# alcohal_sensor_and_send_sms_using_gsm.net
KiCad netlist of a schematic drawn in EAGLE
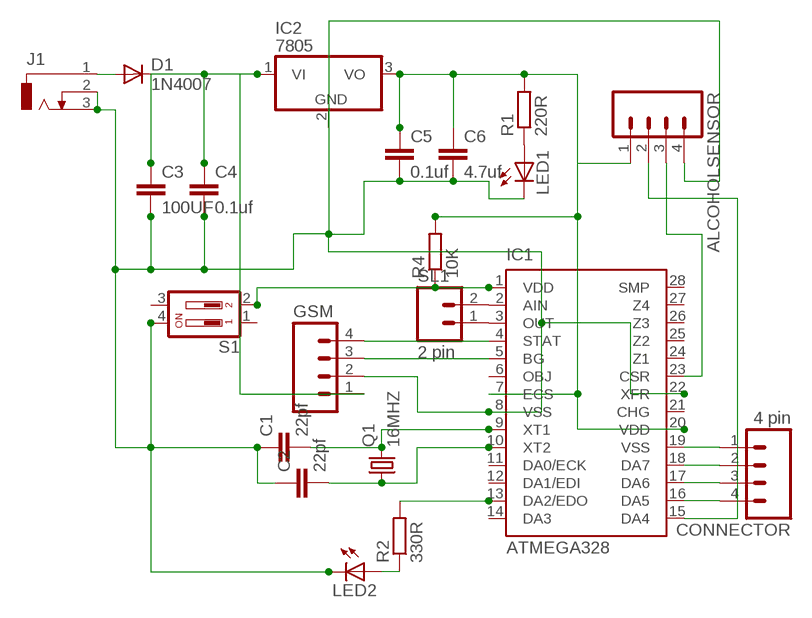
[diagram p0: schematic, sheet 1]

(export (version "E")
  (design (tool "Eeschema 10.0.6"))
  (components
    (comp (ref "ALCOHOLSENSOR")
      (value "M04")
      (footprint "eagle-import:04P")
      (fields (field (name "OC_FARNELL") "unknown") (field (name "OC_NEWARK") "unknown"))
      (libsource (lib "eagle-import") (part "M04"))
    )
    (comp (ref "C1")
      (value "22pf")
      (footprint "eagle-import:C2.5-2")
      (libsource (lib "eagle-import") (part "C2.5/2"))
    )
    (comp (ref "C2")
      (value "22pf")
      (footprint "eagle-import:C2.5-2")
      (libsource (lib "eagle-import") (part "C2.5/2"))
    )
    (comp (ref "C3")
      (value "100UF")
      (footprint "eagle-import:C2.5-2")
      (libsource (lib "eagle-import") (part "C2.5/2"))
    )
    (comp (ref "C4")
      (value "0.1uf")
      (footprint "eagle-import:C2.5-2")
      (libsource (lib "eagle-import") (part "C2.5/2"))
    )
    (comp (ref "C5")
      (value "0.1uf")
      (footprint "eagle-import:C2.5-2")
      (libsource (lib "eagle-import") (part "C2.5/2"))
    )
    (comp (ref "C6")
      (value "4.7uf")
      (footprint "eagle-import:C2.5-2")
      (libsource (lib "eagle-import") (part "C2.5/2"))
    )
    (comp (ref "CONNECTOR")
      (value "4 pin")
      (footprint "eagle-import:04P")
      (fields (field (name "OC_FARNELL") "unknown") (field (name "OC_NEWARK") "unknown"))
      (libsource (lib "eagle-import") (part "M04"))
    )
    (comp (ref "D1")
      (value "1N4007")
      (footprint "eagle-import:DO41-10")
      (libsource (lib "eagle-import") (part "1N4004"))
    )
    (comp (ref "GSM")
      (value "M04")
      (footprint "eagle-import:04P")
      (libsource (lib "eagle-import") (part "M04"))
    )
    (comp (ref "IC1")
      (value "ATMEGA328")
      (footprint "eagle-import:DIL28-3")
      (libsource (lib "eagle-import") (part "QT9701BD"))
    )
    (comp (ref "IC2")
      (value "7805")
      (footprint "eagle-import:TO220V")
      (libsource (lib "eagle-import") (part "78TV6"))
    )
    (comp (ref "J1")
      (value "DCJ0303")
      (footprint "eagle-import:DCJ0303")
      (libsource (lib "eagle-import") (part "DCJ0303"))
    )
    (comp (ref "LED1")
      (value "LED3MM")
      (footprint "eagle-import:LED3MM")
      (libsource (lib "eagle-import") (part "LED3MM"))
    )
    (comp (ref "LED2")
      (value "LED3MM")
      (footprint "eagle-import:LED3MM")
      (libsource (lib "eagle-import") (part "LED3MM"))
    )
    (comp (ref "Q1")
      (value "16MHZ")
      (footprint "eagle-import:HC49_S")
      (libsource (lib "eagle-import") (part "CRYSTALHC49S"))
    )
    (comp (ref "R1")
      (value "220R")
      (footprint "eagle-import:0207_10")
      (libsource (lib "eagle-import") (part "R-EU_0207/10"))
    )
    (comp (ref "R2")
      (value "330R")
      (footprint "eagle-import:0207_10")
      (libsource (lib "eagle-import") (part "R-EU_0207/10"))
    )
    (comp (ref "R4")
      (value "10K")
      (footprint "eagle-import:0207_10")
      (libsource (lib "eagle-import") (part "R-EU_0207/10"))
    )
    (comp (ref "S1")
      (value "DP02")
      (footprint "eagle-import:DP-02")
      (fields (field (name "MPN") "MCDP02"))
      (libsource (lib "eagle-import") (part "DP02"))
    )
    (comp (ref "SL1")
      (value "2 pin")
      (footprint "eagle-import:02P")
      (libsource (lib "eagle-import") (part "M02"))
    )
  )
  (nets
    (net (code "1") (name "Net-(CONNECTOR-Pad1)") (class "Default")
      (node (ref "CONNECTOR") (pin "1") (pinfunction "1_1") (pintype "passive"))
      (node (ref "IC1") (pin "19") (pinfunction "VSS_19") (pintype "input"))
    )
    (net (code "2") (name "Net-(D1-PadA)") (class "Default")
      (node (ref "D1") (pin "A") (pinfunction "A_A") (pintype "passive"))
      (node (ref "J1") (pin "1") (pinfunction "1_1") (pintype "passive"))
    )
    (net (code "3") (name "Net-(IC1-AIN)") (class "Default")
      (node (ref "IC1") (pin "2") (pinfunction "AIN_2") (pintype "input"))
      (node (ref "SL1") (pin "2") (pinfunction "2_2") (pintype "passive"))
    )
    (net (code "4") (name "Net-(IC1-BG)") (class "Default")
      (node (ref "GSM") (pin "3") (pinfunction "3_3") (pintype "passive"))
      (node (ref "IC1") (pin "5") (pinfunction "BG_5") (pintype "input"))
    )
    (net (code "5") (name "Net-(IC1-CSR)") (class "Default")
      (node (ref "ALCOHOLSENSOR") (pin "3") (pinfunction "3_3") (pintype "passive"))
      (node (ref "IC1") (pin "23") (pinfunction "CSR_23") (pintype "output"))
    )
    (net (code "6") (name "Net-(IC1-DA2{slash}EDO)") (class "Default")
      (node (ref "IC1") (pin "13") (pinfunction "DA2/EDO_13") (pintype "output"))
      (node (ref "R2") (pin "2") (pinfunction "2_2") (pintype "passive"))
    )
    (net (code "7") (name "Net-(IC1-DA4)") (class "Default")
      (node (ref "ALCOHOLSENSOR") (pin "2") (pinfunction "2_2") (pintype "passive"))
      (node (ref "IC1") (pin "15") (pinfunction "DA4_15") (pintype "output"))
    )
    (net (code "8") (name "Net-(IC1-DA5)") (class "Default")
      (node (ref "CONNECTOR") (pin "4") (pinfunction "4_4") (pintype "passive"))
      (node (ref "IC1") (pin "16") (pinfunction "DA5_16") (pintype "output"))
    )
    (net (code "9") (name "Net-(IC1-DA6)") (class "Default")
      (node (ref "CONNECTOR") (pin "3") (pinfunction "3_3") (pintype "passive"))
      (node (ref "IC1") (pin "17") (pinfunction "DA6_17") (pintype "output"))
    )
    (net (code "10") (name "Net-(IC1-DA7)") (class "Default")
      (node (ref "CONNECTOR") (pin "2") (pinfunction "2_2") (pintype "passive"))
      (node (ref "IC1") (pin "18") (pinfunction "DA7_18") (pintype "output"))
    )
    (net (code "11") (name "Net-(IC1-ECS)") (class "Default")
      (node (ref "ALCOHOLSENSOR") (pin "1") (pinfunction "1_1") (pintype "passive"))
      (node (ref "C5") (pin "1") (pinfunction "1_1") (pintype "passive"))
      (node (ref "C6") (pin "1") (pinfunction "1_1") (pintype "passive"))
      (node (ref "IC1") (pin "20") (pinfunction "VDD_20") (pintype "input"))
      (node (ref "IC1") (pin "7") (pinfunction "ECS_7") (pintype "output"))
      (node (ref "IC2") (pin "3") (pinfunction "VO_3") (pintype "passive"))
      (node (ref "R1") (pin "2") (pinfunction "2_2") (pintype "passive"))
      (node (ref "R4") (pin "2") (pinfunction "2_2") (pintype "passive"))
    )
    (net (code "12") (name "Net-(IC1-OUT)") (class "Default")
      (node (ref "IC1") (pin "3") (pinfunction "OUT_3") (pintype "output"))
      (node (ref "SL1") (pin "1") (pinfunction "1_1") (pintype "passive"))
    )
    (net (code "13") (name "Net-(IC1-STAT)") (class "Default")
      (node (ref "GSM") (pin "4") (pinfunction "4_4") (pintype "passive"))
      (node (ref "IC1") (pin "4") (pinfunction "STAT_4") (pintype "output"))
    )
    (net (code "14") (name "Net-(IC1-VDD-Pad1)") (class "Default")
      (node (ref "IC1") (pin "1") (pinfunction "VDD_1") (pintype "input"))
      (node (ref "R4") (pin "1") (pinfunction "1_1") (pintype "passive"))
      (node (ref "S1") (pin "2") (pinfunction "2_2") (pintype "passive"))
    )
    (net (code "15") (name "Net-(IC1-XFR)") (class "Default")
      (node (ref "ALCOHOLSENSOR") (pin "4") (pinfunction "4_4") (pintype "passive"))
      (node (ref "C1") (pin "1") (pinfunction "1_1") (pintype "passive"))
      (node (ref "C2") (pin "1") (pinfunction "1_1") (pintype "passive"))
      (node (ref "C3") (pin "2") (pinfunction "2_2") (pintype "passive"))
      (node (ref "C4") (pin "2") (pinfunction "2_2") (pintype "passive"))
      (node (ref "C5") (pin "2") (pinfunction "2_2") (pintype "passive"))
      (node (ref "C6") (pin "2") (pinfunction "2_2") (pintype "passive"))
      (node (ref "GSM") (pin "2") (pinfunction "2_2") (pintype "passive"))
      (node (ref "IC1") (pin "22") (pinfunction "XFR_22") (pintype "output"))
      (node (ref "IC1") (pin "8") (pinfunction "VSS_8") (pintype "input"))
      (node (ref "IC2") (pin "2") (pinfunction "GND_2") (pintype "passive"))
      (node (ref "J1") (pin "2") (pinfunction "2_2") (pintype "passive"))
      (node (ref "J1") (pin "3") (pinfunction "3_3") (pintype "passive"))
      (node (ref "LED1") (pin "K") (pinfunction "C_K") (pintype "passive"))
      (node (ref "LED2") (pin "K") (pinfunction "C_K") (pintype "passive"))
      (node (ref "S1") (pin "4") (pinfunction "4_4") (pintype "passive"))
    )
    (net (code "16") (name "Net-(IC1-XT1)") (class "Default")
      (node (ref "C1") (pin "2") (pinfunction "2_2") (pintype "passive"))
      (node (ref "IC1") (pin "9") (pinfunction "XT1_9") (pintype "input"))
      (node (ref "Q1") (pin "2") (pinfunction "2_2") (pintype "passive"))
    )
    (net (code "17") (name "Net-(IC1-XT2)") (class "Default")
      (node (ref "C2") (pin "2") (pinfunction "2_2") (pintype "passive"))
      (node (ref "IC1") (pin "10") (pinfunction "XT2_10") (pintype "output"))
      (node (ref "Q1") (pin "1") (pinfunction "1_1") (pintype "passive"))
    )
    (net (code "18") (name "Net-(IC2-VI)") (class "Default")
      (node (ref "C3") (pin "1") (pinfunction "1_1") (pintype "passive"))
      (node (ref "C4") (pin "1") (pinfunction "1_1") (pintype "passive"))
      (node (ref "D1") (pin "C") (pinfunction "C_C") (pintype "passive"))
      (node (ref "GSM") (pin "1") (pinfunction "1_1") (pintype "passive"))
      (node (ref "IC2") (pin "1") (pinfunction "VI_1") (pintype "input"))
    )
    (net (code "19") (name "Net-(LED1-PadA)") (class "Default")
      (node (ref "LED1") (pin "A") (pinfunction "A_A") (pintype "passive"))
      (node (ref "R1") (pin "1") (pinfunction "1_1") (pintype "passive"))
    )
    (net (code "20") (name "Net-(LED2-PadA)") (class "Default")
      (node (ref "LED2") (pin "A") (pinfunction "A_A") (pintype "passive"))
      (node (ref "R2") (pin "1") (pinfunction "1_1") (pintype "passive"))
    )
    (net (code "21") (name "unconnected-(IC1-CHG-Pad21)") (class "Default")
      (node (ref "IC1") (pin "21") (pinfunction "CHG_21") (pintype "output"))
    )
    (net (code "22") (name "unconnected-(IC1-DA0{slash}ECK-Pad11)") (class "Default")
      (node (ref "IC1") (pin "11") (pinfunction "DA0/ECK_11") (pintype "output"))
    )
    (net (code "23") (name "unconnected-(IC1-DA1{slash}EDI-Pad12)") (class "Default")
      (node (ref "IC1") (pin "12") (pinfunction "DA1/EDI_12") (pintype "output"))
    )
    (net (code "24") (name "unconnected-(IC1-DA3-Pad14)") (class "Default")
      (node (ref "IC1") (pin "14") (pinfunction "DA3_14") (pintype "output"))
    )
    (net (code "25") (name "unconnected-(IC1-OBJ-Pad6)") (class "Default")
      (node (ref "IC1") (pin "6") (pinfunction "OBJ_6") (pintype "input"))
    )
    (net (code "26") (name "unconnected-(IC1-SMP-Pad28)") (class "Default")
      (node (ref "IC1") (pin "28") (pinfunction "SMP_28") (pintype "output"))
    )
    (net (code "27") (name "unconnected-(IC1-Z1-Pad24)") (class "Default")
      (node (ref "IC1") (pin "24") (pinfunction "Z1_24") (pintype "output"))
    )
    (net (code "28") (name "unconnected-(IC1-Z2-Pad25)") (class "Default")
      (node (ref "IC1") (pin "25") (pinfunction "Z2_25") (pintype "output"))
    )
    (net (code "29") (name "unconnected-(IC1-Z3-Pad26)") (class "Default")
      (node (ref "IC1") (pin "26") (pinfunction "Z3_26") (pintype "output"))
    )
    (net (code "30") (name "unconnected-(IC1-Z4-Pad27)") (class "Default")
      (node (ref "IC1") (pin "27") (pinfunction "Z4_27") (pintype "output"))
    )
    (net (code "31") (name "unconnected-(S1-Pad1)") (class "Default")
      (node (ref "S1") (pin "1") (pinfunction "1_1") (pintype "passive"))
    )
    (net (code "32") (name "unconnected-(S1-Pad3)") (class "Default")
      (node (ref "S1") (pin "3") (pinfunction "3_3") (pintype "passive"))
    )
  )
)
